# el_wirecontroller.net
KiCad netlist of a schematic drawn in EAGLE
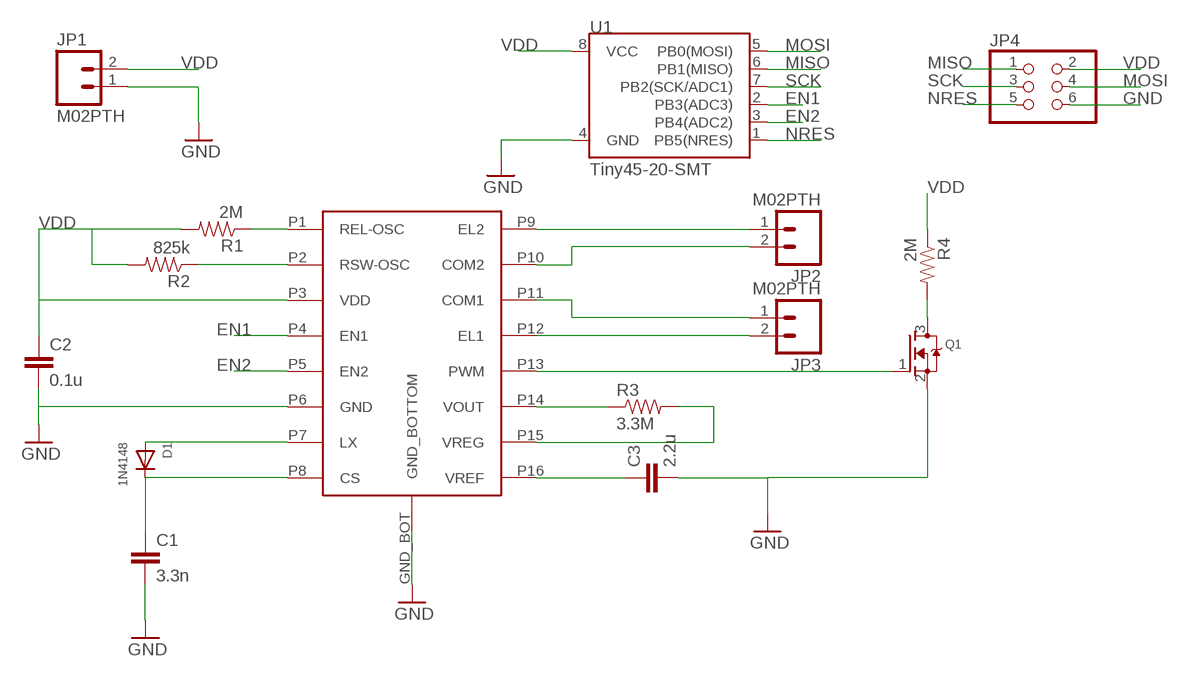
[diagram p0: schematic, sheet 1]

(export (version "E")
  (design (tool "Eeschema 10.0.6"))
  (components
    (comp (ref "C1")
      (value "3.3n")
      (footprint "eagle-import:0402-CAP")
      (libsource (lib "eagle-import") (part "CAP0402-CAP"))
    )
    (comp (ref "C2")
      (value "0.1u")
      (footprint "eagle-import:0402-CAP")
      (libsource (lib "eagle-import") (part "CAP0402-CAP"))
    )
    (comp (ref "C3")
      (value "2.2u")
      (footprint "eagle-import:0402-CAP")
      (libsource (lib "eagle-import") (part "CAP0402-CAP"))
    )
    (comp (ref "D1")
      (value "1N4148")
      (footprint "eagle-import:DO-1N4148")
      (libsource (lib "eagle-import") (part "DIODEDO-1N4148"))
    )
    (comp (ref "JP1")
      (value "M02PTH")
      (footprint "eagle-import:1X02")
      (libsource (lib "eagle-import") (part "M02PTH"))
    )
    (comp (ref "JP2")
      (value "M02PTH")
      (footprint "eagle-import:1X02")
      (libsource (lib "eagle-import") (part "M02PTH"))
    )
    (comp (ref "JP3")
      (value "M02PTH")
      (footprint "eagle-import:1X02")
      (libsource (lib "eagle-import") (part "M02PTH"))
    )
    (comp (ref "JP4")
      (value "PINHD-2X3")
      (footprint "eagle-import:2X03")
      (libsource (lib "eagle-import") (part "PINHD-2X3"))
    )
    (comp (ref "Q1")
      (value "MOSFET-NREFLOW")
      (footprint "eagle-import:SOT23")
      (libsource (lib "eagle-import") (part "MOSFET-NREFLOW"))
    )
    (comp (ref "R1")
      (value "2M")
      (footprint "eagle-import:0402-RES")
      (libsource (lib "eagle-import") (part "RESISTOR0402-RES"))
    )
    (comp (ref "R2")
      (value "825k")
      (footprint "eagle-import:0402-RES")
      (libsource (lib "eagle-import") (part "RESISTOR0402-RES"))
    )
    (comp (ref "R3")
      (value "3.3M")
      (footprint "eagle-import:0402-RES")
      (libsource (lib "eagle-import") (part "RESISTOR0402-RES"))
    )
    (comp (ref "R4")
      (value "2M")
      (footprint "eagle-import:0402-RES")
      (libsource (lib "eagle-import") (part "RESISTOR0402-RES"))
    )
    (comp (ref "U$1")
      (value "HV861")
      (footprint "eagle-import:QFN-16")
      (libsource (lib "eagle-import") (part "HV861"))
    )
    (comp (ref "U1")
      (value "Tiny45-20-SMT")
      (footprint "eagle-import:SO08-EIAJ")
      (libsource (lib "eagle-import") (part "ATTINY45TINY45-20-SMT"))
    )
  )
  (nets
    (net (code "1") (name "/EN1") (class "Default")
      (node (ref "U$1") (pin "P4") (pinfunction "EN1_P4") (pintype "bidirectional"))
      (node (ref "U1") (pin "2") (pinfunction "PB3(ADC3)_2") (pintype "bidirectional"))
    )
    (net (code "2") (name "/EN2") (class "Default")
      (node (ref "U$1") (pin "P5") (pinfunction "EN2_P5") (pintype "bidirectional"))
      (node (ref "U1") (pin "3") (pinfunction "PB4(ADC2)_3") (pintype "bidirectional"))
    )
    (net (code "3") (name "/MISO") (class "Default")
      (node (ref "JP4") (pin "1") (pinfunction "1_1") (pintype "passive"))
      (node (ref "U1") (pin "6") (pinfunction "PB1(MISO)_6") (pintype "bidirectional"))
    )
    (net (code "4") (name "/MOSI") (class "Default")
      (node (ref "JP4") (pin "4") (pinfunction "4_4") (pintype "passive"))
      (node (ref "U1") (pin "5") (pinfunction "PB0(MOSI)_5") (pintype "bidirectional"))
    )
    (net (code "5") (name "/NRES") (class "Default")
      (node (ref "JP4") (pin "5") (pinfunction "5_5") (pintype "passive"))
      (node (ref "U1") (pin "1") (pinfunction "PB5(NRES)_1") (pintype "bidirectional"))
    )
    (net (code "6") (name "/SCK") (class "Default")
      (node (ref "JP4") (pin "3") (pinfunction "3_3") (pintype "passive"))
      (node (ref "U1") (pin "7") (pinfunction "PB2(SCK/ADC1)_7") (pintype "bidirectional"))
    )
    (net (code "7") (name "/VDD") (class "Default")
      (node (ref "C2") (pin "1") (pinfunction "1_1") (pintype "passive"))
      (node (ref "JP1") (pin "2") (pinfunction "2_2") (pintype "passive"))
      (node (ref "JP4") (pin "2") (pinfunction "2_2") (pintype "passive"))
      (node (ref "R1") (pin "2") (pinfunction "2_2") (pintype "passive"))
      (node (ref "R2") (pin "2") (pinfunction "2_2") (pintype "passive"))
      (node (ref "R4") (pin "1") (pinfunction "1_1") (pintype "passive"))
      (node (ref "U$1") (pin "P3") (pinfunction "VDD_P3") (pintype "bidirectional"))
      (node (ref "U1") (pin "8") (pinfunction "VCC_8") (pintype "bidirectional"))
    )
    (net (code "8") (name "GND") (class "Default")
      (node (ref "C1") (pin "2") (pinfunction "2_2") (pintype "passive"))
      (node (ref "C2") (pin "2") (pinfunction "2_2") (pintype "passive"))
      (node (ref "C3") (pin "2") (pinfunction "2_2") (pintype "passive"))
      (node (ref "JP1") (pin "1") (pinfunction "1_1") (pintype "passive"))
      (node (ref "JP4") (pin "6") (pinfunction "6_6") (pintype "passive"))
      (node (ref "Q1") (pin "2") (pinfunction "S_2") (pintype "bidirectional"))
      (node (ref "U$1") (pin "GND_BOT") (pinfunction "GND_BOTTOM_GND_BOT") (pintype "bidirectional"))
      (node (ref "U$1") (pin "P6") (pinfunction "GND_P6") (pintype "bidirectional"))
      (node (ref "U1") (pin "4") (pinfunction "GND_4") (pintype "bidirectional"))
    )
    (net (code "9") (name "Net-(Q1-D)") (class "Default")
      (node (ref "Q1") (pin "3") (pinfunction "D_3") (pintype "bidirectional"))
      (node (ref "R4") (pin "2") (pinfunction "2_2") (pintype "passive"))
    )
    (net (code "10") (name "Net-(Q1-G)") (class "Default")
      (node (ref "Q1") (pin "1") (pinfunction "G_1") (pintype "bidirectional"))
      (node (ref "U$1") (pin "P13") (pinfunction "PWM_P13") (pintype "bidirectional"))
    )
    (net (code "11") (name "Net-(U$1-COM1)") (class "Default")
      (node (ref "JP3") (pin "1") (pinfunction "1_1") (pintype "passive"))
      (node (ref "U$1") (pin "P11") (pinfunction "COM1_P11") (pintype "bidirectional"))
    )
    (net (code "12") (name "Net-(U$1-COM2)") (class "Default")
      (node (ref "JP2") (pin "2") (pinfunction "2_2") (pintype "passive"))
      (node (ref "U$1") (pin "P10") (pinfunction "COM2_P10") (pintype "bidirectional"))
    )
    (net (code "13") (name "Net-(U$1-CS)") (class "Default")
      (node (ref "C1") (pin "1") (pinfunction "1_1") (pintype "passive"))
      (node (ref "D1") (pin "C") (pinfunction "C_C") (pintype "passive"))
      (node (ref "U$1") (pin "P8") (pinfunction "CS_P8") (pintype "bidirectional"))
    )
    (net (code "14") (name "Net-(U$1-EL1)") (class "Default")
      (node (ref "JP3") (pin "2") (pinfunction "2_2") (pintype "passive"))
      (node (ref "U$1") (pin "P12") (pinfunction "EL1_P12") (pintype "bidirectional"))
    )
    (net (code "15") (name "Net-(U$1-EL2)") (class "Default")
      (node (ref "JP2") (pin "1") (pinfunction "1_1") (pintype "passive"))
      (node (ref "U$1") (pin "P9") (pinfunction "EL2_P9") (pintype "bidirectional"))
    )
    (net (code "16") (name "Net-(U$1-LX)") (class "Default")
      (node (ref "D1") (pin "A") (pinfunction "A_A") (pintype "passive"))
      (node (ref "U$1") (pin "P7") (pinfunction "LX_P7") (pintype "bidirectional"))
    )
    (net (code "17") (name "Net-(U$1-REL-OSC)") (class "Default")
      (node (ref "R1") (pin "1") (pinfunction "1_1") (pintype "passive"))
      (node (ref "U$1") (pin "P1") (pinfunction "REL-OSC_P1") (pintype "bidirectional"))
    )
    (net (code "18") (name "Net-(U$1-RSW-OSC)") (class "Default")
      (node (ref "R2") (pin "1") (pinfunction "1_1") (pintype "passive"))
      (node (ref "U$1") (pin "P2") (pinfunction "RSW-OSC_P2") (pintype "bidirectional"))
    )
    (net (code "19") (name "Net-(U$1-VOUT)") (class "Default")
      (node (ref "R3") (pin "1") (pinfunction "1_1") (pintype "passive"))
      (node (ref "U$1") (pin "P14") (pinfunction "VOUT_P14") (pintype "bidirectional"))
    )
    (net (code "20") (name "Net-(U$1-VREF)") (class "Default")
      (node (ref "C3") (pin "1") (pinfunction "1_1") (pintype "passive"))
      (node (ref "U$1") (pin "P16") (pinfunction "VREF_P16") (pintype "bidirectional"))
    )
    (net (code "21") (name "Net-(U$1-VREG)") (class "Default")
      (node (ref "R3") (pin "2") (pinfunction "2_2") (pintype "passive"))
      (node (ref "U$1") (pin "P15") (pinfunction "VREG_P15") (pintype "bidirectional"))
    )
  )
)
